# SENSE.net
KiCad netlist of a schematic drawn in Altium Designer
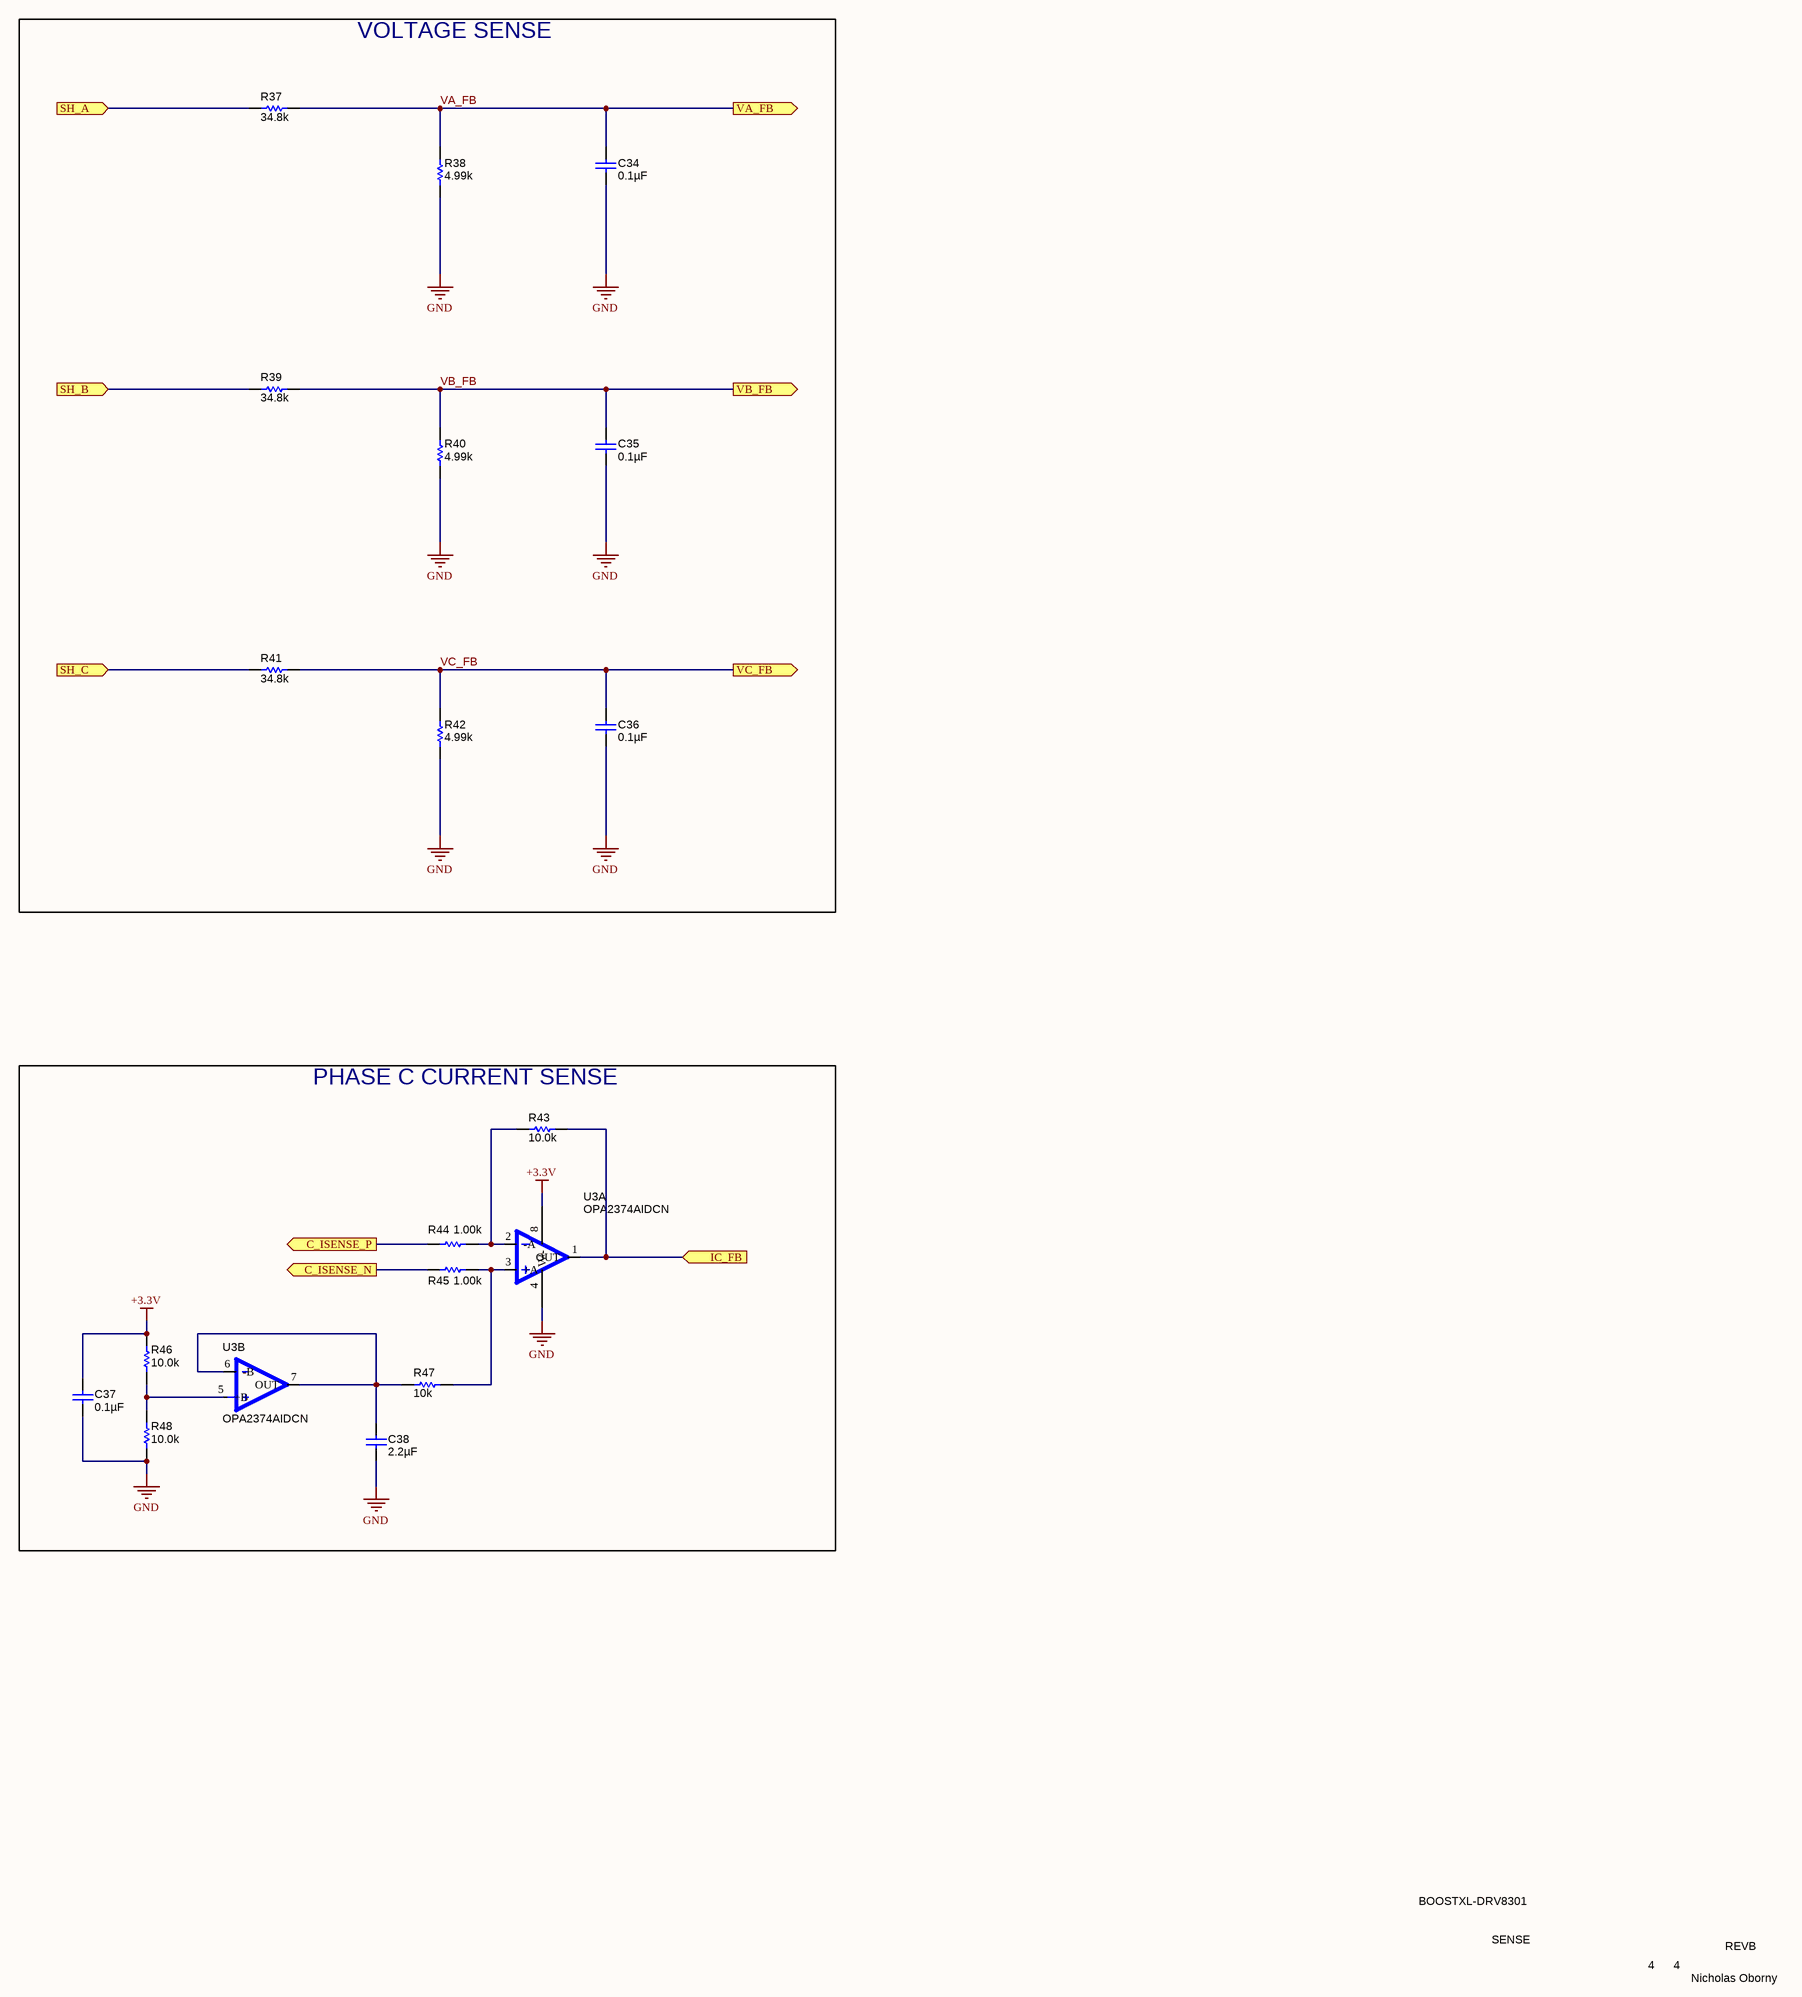
[diagram p0: SENSE.SchDoc]

(export (version "E")
  (design (tool "Eeschema 10.0.6"))
  (components
    (comp (ref "C34")
      (value "C0603C104J4RACTU")
      (footprint "0603L")
      (description "CAP, CERM, 0.1uF, 16V, +/-5%, X7R, 0603")
      (fields
        (field (name "VALUEDISPLAYED") "0.1µF")
        (field (name "MANUFACTURER") "Kemet")
        (field (name "PUBLISHER") "Texas Instruments")
      )
      (libsource (lib "Capacitor_Ceramic") (part "C0603C104J4RACTU"))
    )
    (comp (ref "C35")
      (value "C0603C104J4RACTU")
      (footprint "0603L")
      (description "CAP, CERM, 0.1uF, 16V, +/-5%, X7R, 0603")
      (fields
        (field (name "VALUEDISPLAYED") "0.1µF")
        (field (name "MANUFACTURER") "Kemet")
        (field (name "PUBLISHER") "Texas Instruments")
      )
      (libsource (lib "Capacitor_Ceramic") (part "C0603C104J4RACTU"))
    )
    (comp (ref "C36")
      (value "C0603C104J4RACTU")
      (footprint "0603L")
      (description "CAP, CERM, 0.1uF, 16V, +/-5%, X7R, 0603")
      (fields
        (field (name "VALUEDISPLAYED") "0.1µF")
        (field (name "MANUFACTURER") "Kemet")
        (field (name "PUBLISHER") "Texas Instruments")
      )
      (libsource (lib "Capacitor_Ceramic") (part "C0603C104J4RACTU"))
    )
    (comp (ref "C37")
      (value "C0603C104J4RACTU")
      (footprint "0603L")
      (description "CAP, CERM, 0.1uF, 16V, +/-5%, X7R, 0603")
      (fields
        (field (name "VALUEDISPLAYED") "0.1µF")
        (field (name "MANUFACTURER") "Kemet")
        (field (name "PUBLISHER") "Texas Instruments")
      )
      (libsource (lib "Capacitor_Ceramic") (part "C0603C104J4RACTU"))
    )
    (comp (ref "C38")
      (value "C0603C225M8PACTU")
      (footprint "0603L")
      (description "CAP, CERM, 2.2uF, 10V, +/-20%, X5R, 0603")
      (fields
        (field (name "VALUEDISPLAYED") "2.2µF")
        (field (name "MANUFACTURER") "Kemet")
        (field (name "PUBLISHER") "Texas Instruments")
      )
      (libsource (lib "Capacitor_Ceramic") (part "C0603C225M8PACTU"))
    )
    (comp (ref "R37")
      (value "34.8k")
      (footprint "0603L")
      (description "RES, 34.8k ohm, 1%, 0.1W, 0603")
      (fields
        (field (name "PARTNUMBER") "CRCW060334K8FKEA")
        (field (name "MANUFACTURER") "Vishay-Dale")
        (field (name "PUBLISHER") "Texas Instruments")
      )
      (libsource (lib "Resistor_0603") (part "CRCW060334K8FKEA"))
    )
    (comp (ref "R38")
      (value "4.99k")
      (footprint "0603L")
      (description "RES, 4.99k ohm, 1%, 0.1W, 0603")
      (fields
        (field (name "PARTNUMBER") "CRCW06034K99FKEA")
        (field (name "MANUFACTURER") "Vishay-Dale")
        (field (name "PUBLISHER") "Texas Instruments")
      )
      (libsource (lib "Resistor_0603") (part "CRCW06034K99FKEA"))
    )
    (comp (ref "R39")
      (value "34.8k")
      (footprint "0603L")
      (description "RES, 34.8k ohm, 1%, 0.1W, 0603")
      (fields
        (field (name "PARTNUMBER") "CRCW060334K8FKEA")
        (field (name "MANUFACTURER") "Vishay-Dale")
        (field (name "PUBLISHER") "Texas Instruments")
      )
      (libsource (lib "Resistor_0603") (part "CRCW060334K8FKEA"))
    )
    (comp (ref "R40")
      (value "4.99k")
      (footprint "0603L")
      (description "RES, 4.99k ohm, 1%, 0.1W, 0603")
      (fields
        (field (name "PARTNUMBER") "CRCW06034K99FKEA")
        (field (name "MANUFACTURER") "Vishay-Dale")
        (field (name "PUBLISHER") "Texas Instruments")
      )
      (libsource (lib "Resistor_0603") (part "CRCW06034K99FKEA"))
    )
    (comp (ref "R41")
      (value "34.8k")
      (footprint "0603L")
      (description "RES, 34.8k ohm, 1%, 0.1W, 0603")
      (fields
        (field (name "PARTNUMBER") "CRCW060334K8FKEA")
        (field (name "MANUFACTURER") "Vishay-Dale")
        (field (name "PUBLISHER") "Texas Instruments")
      )
      (libsource (lib "Resistor_0603") (part "CRCW060334K8FKEA"))
    )
    (comp (ref "R42")
      (value "4.99k")
      (footprint "0603L")
      (description "RES, 4.99k ohm, 1%, 0.1W, 0603")
      (fields
        (field (name "PARTNUMBER") "CRCW06034K99FKEA")
        (field (name "MANUFACTURER") "Vishay-Dale")
        (field (name "PUBLISHER") "Texas Instruments")
      )
      (libsource (lib "Resistor_0603") (part "CRCW06034K99FKEA"))
    )
    (comp (ref "R43")
      (value "10.0k")
      (footprint "0603L")
      (description "RES, 10.0k ohm, 0.1%, 0.1W, 0603")
      (fields
        (field (name "PARTNUMBER") "RG1608P-103-B-T5")
        (field (name "MANUFACTURER") "Susumu Co Ltd")
        (field (name "PUBLISHER") "Texas Instruments")
      )
      (libsource (lib "Resistor_0603") (part "RG1608P-103-B-T5"))
    )
    (comp (ref "R44")
      (value "1.00k")
      (footprint "0603L")
      (description "RES, 1.00k ohm, 1%, 0.1W, 0603")
      (fields
        (field (name "PARTNUMBER") "CRCW06031K00FKEA")
        (field (name "MANUFACTURER") "Vishay-Dale")
        (field (name "PUBLISHER") "Texas Instruments")
      )
      (libsource (lib "Resistor_0603") (part "CRCW06031K00FKEA"))
    )
    (comp (ref "R45")
      (value "1.00k")
      (footprint "0603L")
      (description "RES, 1.00k ohm, 1%, 0.1W, 0603")
      (fields
        (field (name "PARTNUMBER") "CRCW06031K00FKEA")
        (field (name "MANUFACTURER") "Vishay-Dale")
        (field (name "PUBLISHER") "Texas Instruments")
      )
      (libsource (lib "Resistor_0603") (part "CRCW06031K00FKEA"))
    )
    (comp (ref "R46")
      (value "10.0k")
      (footprint "0603L")
      (description "RES, 10.0k ohm, 0.1%, 0.1W, 0603")
      (fields
        (field (name "PARTNUMBER") "RG1608P-103-B-T5")
        (field (name "MANUFACTURER") "Susumu Co Ltd")
        (field (name "PUBLISHER") "Texas Instruments")
      )
      (libsource (lib "Resistor_0603") (part "RG1608P-103-B-T5"))
    )
    (comp (ref "R47")
      (value "10k")
      (footprint "0603L")
      (description "RES, 10k ohm, 5%, 0.1W, 0603")
      (fields
        (field (name "PARTNUMBER") "CRCW060310K0JNEA")
        (field (name "MANUFACTURER") "Vishay-Dale")
        (field (name "PUBLISHER") "Texas Instruments")
      )
      (libsource (lib "Resistor_0603") (part "CRCW060310K0JNEA"))
    )
    (comp (ref "R48")
      (value "10.0k")
      (footprint "0603L")
      (description "RES, 10.0k ohm, 0.1%, 0.1W, 0603")
      (fields
        (field (name "PARTNUMBER") "RG1608P-103-B-T5")
        (field (name "MANUFACTURER") "Susumu Co Ltd")
        (field (name "PUBLISHER") "Texas Instruments")
      )
      (libsource (lib "Resistor_0603") (part "RG1608P-103-B-T5"))
    )
    (comp (ref "U3")
      (value "OPA2374AIDCN")
      (footprint "DCN")
      (description "IC, CMOS, R-R I/O  Op Amp, Single Supply, 6.5MHz, 585uA")
      (fields (field (name "MANUFACTURER") "TI"))
      (libsource (lib "PADSlegacy_Active") (part "OPA2374AIDCN"))
    )
  )
  (nets
    (net (code "1") (name "+3.3V") (class "Default")
      (node (ref "C37") (pin "1") (pinfunction "1_1") (pintype "passive"))
      (node (ref "R46") (pin "2") (pinfunction "2_2") (pintype "passive"))
      (node (ref "U3") (pin "8") (pinfunction "V+_8") (pintype "passive"))
    )
    (net (code "2") (name "/C_ISENSE_N") (class "Default")
      (node (ref "R45") (pin "1") (pinfunction "1_1") (pintype "passive"))
    )
    (net (code "3") (name "/C_ISENSE_P") (class "Default")
      (node (ref "R44") (pin "1") (pinfunction "1_1") (pintype "passive"))
    )
    (net (code "4") (name "/IC_FB") (class "Default")
      (node (ref "R43") (pin "2") (pinfunction "2_2") (pintype "passive"))
      (node (ref "U3") (pin "1") (pinfunction "OUT_1") (pintype "passive"))
    )
    (net (code "5") (name "/SH_A") (class "Default")
      (node (ref "R37") (pin "1") (pinfunction "1_1") (pintype "passive"))
    )
    (net (code "6") (name "/SH_B") (class "Default")
      (node (ref "R39") (pin "1") (pinfunction "1_1") (pintype "passive"))
    )
    (net (code "7") (name "/SH_C") (class "Default")
      (node (ref "R41") (pin "1") (pinfunction "1_1") (pintype "passive"))
    )
    (net (code "8") (name "/VA_FB") (class "Default")
      (node (ref "C34") (pin "1") (pinfunction "1_1") (pintype "passive"))
      (node (ref "R37") (pin "2") (pinfunction "2_2") (pintype "passive"))
      (node (ref "R38") (pin "2") (pinfunction "2_2") (pintype "passive"))
    )
    (net (code "9") (name "/VB_FB") (class "Default")
      (node (ref "C35") (pin "1") (pinfunction "1_1") (pintype "passive"))
      (node (ref "R39") (pin "2") (pinfunction "2_2") (pintype "passive"))
      (node (ref "R40") (pin "2") (pinfunction "2_2") (pintype "passive"))
    )
    (net (code "10") (name "/VC_FB") (class "Default")
      (node (ref "C36") (pin "1") (pinfunction "1_1") (pintype "passive"))
      (node (ref "R41") (pin "2") (pinfunction "2_2") (pintype "passive"))
      (node (ref "R42") (pin "2") (pinfunction "2_2") (pintype "passive"))
    )
    (net (code "11") (name "GND") (class "Default")
      (node (ref "C34") (pin "2") (pinfunction "2_2") (pintype "passive"))
      (node (ref "C35") (pin "2") (pinfunction "2_2") (pintype "passive"))
      (node (ref "C36") (pin "2") (pinfunction "2_2") (pintype "passive"))
      (node (ref "C37") (pin "2") (pinfunction "2_2") (pintype "passive"))
      (node (ref "C38") (pin "2") (pinfunction "2_2") (pintype "passive"))
      (node (ref "R38") (pin "1") (pinfunction "1_1") (pintype "passive"))
      (node (ref "R40") (pin "1") (pinfunction "1_1") (pintype "passive"))
      (node (ref "R42") (pin "1") (pinfunction "1_1") (pintype "passive"))
      (node (ref "R48") (pin "1") (pinfunction "1_1") (pintype "passive"))
      (node (ref "U3") (pin "4") (pinfunction "V-_4") (pintype "passive"))
    )
    (net (code "12") (name "Net-(U3A-+A)") (class "Default")
      (node (ref "R45") (pin "2") (pinfunction "2_2") (pintype "passive"))
      (node (ref "R47") (pin "2") (pinfunction "2_2") (pintype "passive"))
      (node (ref "U3") (pin "3") (pinfunction "+A_3") (pintype "passive"))
    )
    (net (code "13") (name "Net-(U3A--A)") (class "Default")
      (node (ref "R43") (pin "1") (pinfunction "1_1") (pintype "passive"))
      (node (ref "R44") (pin "2") (pinfunction "2_2") (pintype "passive"))
      (node (ref "U3") (pin "2") (pinfunction "-A_2") (pintype "passive"))
    )
    (net (code "14") (name "Net-(U3B-+B)") (class "Default")
      (node (ref "R46") (pin "1") (pinfunction "1_1") (pintype "passive"))
      (node (ref "R48") (pin "2") (pinfunction "2_2") (pintype "passive"))
      (node (ref "U3") (pin "5") (pinfunction "+B_5") (pintype "passive"))
    )
    (net (code "15") (name "Net-(U3B--B)") (class "Default")
      (node (ref "C38") (pin "1") (pinfunction "1_1") (pintype "passive"))
      (node (ref "R47") (pin "1") (pinfunction "1_1") (pintype "passive"))
      (node (ref "U3") (pin "6") (pinfunction "-B_6") (pintype "passive"))
      (node (ref "U3") (pin "7") (pinfunction "OUT_7") (pintype "passive"))
    )
  )
)
